# SCH_ralay.net
KiCad netlist of a schematic drawn in EasyEDA
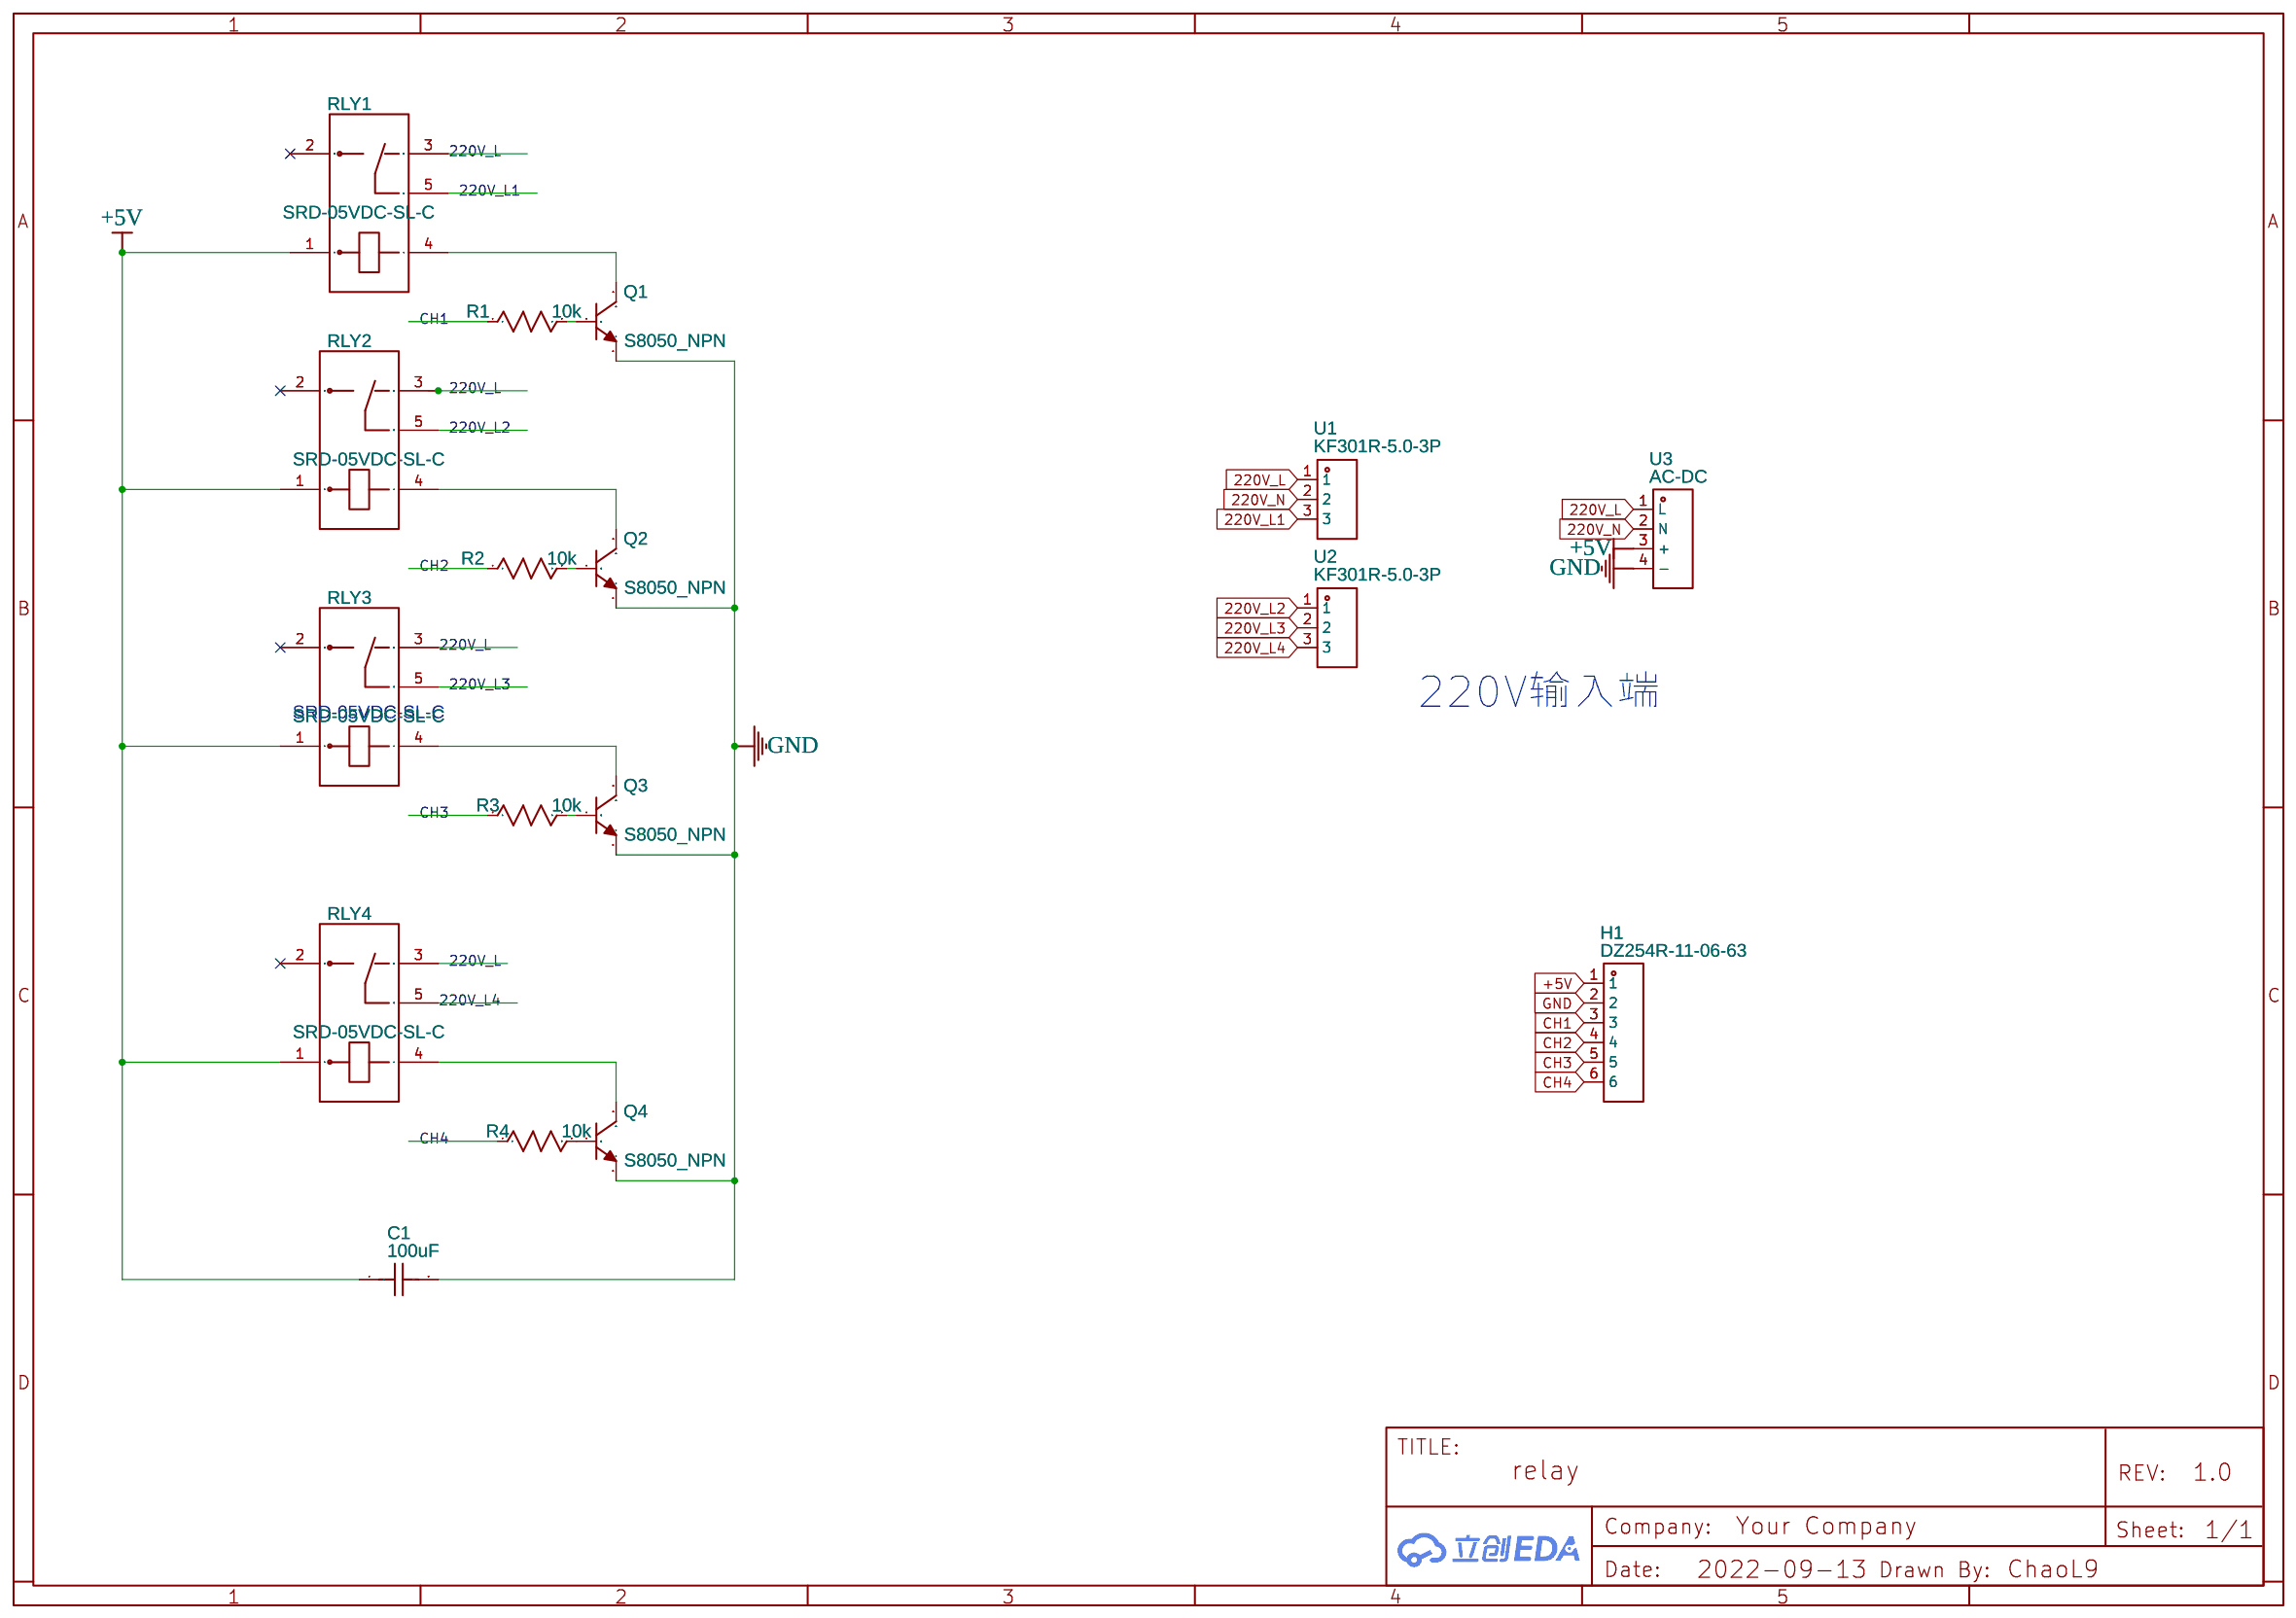
[diagram p0: schematic sheet]

(export (version "E")
  (design (tool "Eeschema 10.0.6"))
  (components
    (comp (ref "C1")
      (value "100uF")
      (fields
        (field (name "BOM_Manufacturer Part") "GRM21BC80E107ME15L")
        (field (name "BOM_Supplier Part") "C2167924")
      )
      (libsource (lib "") (part "GRM21BC80E107ME15L"))
    )
    (comp (ref "H1")
      (value "DZ254R-11-06-63")
      (fields (field (name "BOM_Supplier Part") "C2935912"))
      (libsource (lib "") (part "DZ254R-11-06-63"))
    )
    (comp (ref "Q1")
      (value "S8050_NPN")
      (fields (field (name "BOM_Manufacturer Part") "S8050") (field (name "BOM_Supplier Part") "C466625"))
      (libsource (lib "") (part "S8050_C466625"))
    )
    (comp (ref "Q2")
      (value "S8050_NPN")
      (fields (field (name "BOM_Manufacturer Part") "S8050") (field (name "BOM_Supplier Part") "C466625"))
      (libsource (lib "") (part "S8050_C466625"))
    )
    (comp (ref "Q3")
      (value "S8050_NPN")
      (fields (field (name "BOM_Manufacturer Part") "S8050") (field (name "BOM_Supplier Part") "C466625"))
      (libsource (lib "") (part "S8050_C466625"))
    )
    (comp (ref "Q4")
      (value "S8050_NPN")
      (fields (field (name "BOM_Manufacturer Part") "S8050") (field (name "BOM_Supplier Part") "C466625"))
      (libsource (lib "") (part "S8050_C466625"))
    )
    (comp (ref "R1") (value "10k") (libsource (lib "") (part "R_0603_US")))
    (comp (ref "R2") (value "10k") (libsource (lib "") (part "R_0603_US")))
    (comp (ref "R3") (value "10k") (libsource (lib "") (part "R_0603_US")))
    (comp (ref "R4") (value "10k") (libsource (lib "") (part "R_0603_US")))
    (comp (ref "RLY1")
      (value "SRD-05VDC-SL-C")
      (fields (field (name "BOM_Supplier Part") "C35449"))
      (libsource (lib "") (part "SRD-05VDC-SL-C"))
    )
    (comp (ref "RLY2")
      (value "SRD-05VDC-SL-C")
      (fields (field (name "BOM_Supplier Part") "C35449"))
      (libsource (lib "") (part "SRD-05VDC-SL-C"))
    )
    (comp (ref "RLY3")
      (value "SRD-05VDC-SL-C")
      (fields (field (name "BOM_Supplier Part") "C35449"))
      (libsource (lib "") (part "SRD-05VDC-SL-C"))
    )
    (comp (ref "RLY4")
      (value "SRD-05VDC-SL-C")
      (fields (field (name "BOM_Supplier Part") "C35449"))
      (libsource (lib "") (part "SRD-05VDC-SL-C"))
    )
    (comp (ref "U1")
      (value "KF301R-5.0-3P")
      (fields (field (name "BOM_Supplier Part") "C474884"))
      (libsource (lib "") (part "KF301R-5.0-3P"))
    )
    (comp (ref "U2")
      (value "KF301R-5.0-3P")
      (fields (field (name "BOM_Supplier Part") "C474884"))
      (libsource (lib "") (part "KF301R-5.0-3P"))
    )
    (comp (ref "U3") (value "AC-DC") (libsource (lib "") (part "AC-DC")))
  )
  (nets
    (net (code "1") (name "+5V") (class "Default")
      (node (ref "C1") (pin "1") (pinfunction "1_1") (pintype "unspecified"))
      (node (ref "H1") (pin "1") (pinfunction "1_1") (pintype "unspecified"))
      (node (ref "RLY1") (pin "1") (pinfunction "1_1") (pintype "input"))
      (node (ref "RLY2") (pin "1") (pinfunction "1_1") (pintype "input"))
      (node (ref "RLY3") (pin "1") (pinfunction "1_1") (pintype "input"))
      (node (ref "RLY4") (pin "1") (pinfunction "1_1") (pintype "input"))
      (node (ref "U3") (pin "3") (pinfunction "+_3") (pintype "unspecified"))
    )
    (net (code "2") (name "220V_L") (class "Default")
      (node (ref "RLY1") (pin "3") (pinfunction "3_3") (pintype "input"))
      (node (ref "RLY2") (pin "3") (pinfunction "3_3") (pintype "input"))
      (node (ref "RLY3") (pin "3") (pinfunction "3_3") (pintype "input"))
      (node (ref "RLY4") (pin "3") (pinfunction "3_3") (pintype "input"))
      (node (ref "U1") (pin "1") (pinfunction "1_1") (pintype "unspecified"))
      (node (ref "U3") (pin "1") (pinfunction "L_1") (pintype "unspecified"))
    )
    (net (code "3") (name "220V_L1") (class "Default")
      (node (ref "RLY1") (pin "5") (pinfunction "5_5") (pintype "input"))
      (node (ref "U1") (pin "3") (pinfunction "3_3") (pintype "unspecified"))
    )
    (net (code "4") (name "220V_L2") (class "Default")
      (node (ref "RLY2") (pin "5") (pinfunction "5_5") (pintype "input"))
      (node (ref "U2") (pin "1") (pinfunction "1_1") (pintype "unspecified"))
    )
    (net (code "5") (name "220V_L3") (class "Default")
      (node (ref "RLY3") (pin "5") (pinfunction "5_5") (pintype "input"))
      (node (ref "U2") (pin "2") (pinfunction "2_2") (pintype "unspecified"))
    )
    (net (code "6") (name "220V_L4") (class "Default")
      (node (ref "RLY4") (pin "5") (pinfunction "5_5") (pintype "input"))
      (node (ref "U2") (pin "3") (pinfunction "3_3") (pintype "unspecified"))
    )
    (net (code "7") (name "220V_N") (class "Default")
      (node (ref "U1") (pin "2") (pinfunction "2_2") (pintype "unspecified"))
      (node (ref "U3") (pin "2") (pinfunction "N_2") (pintype "unspecified"))
    )
    (net (code "8") (name "CH1") (class "Default")
      (node (ref "H1") (pin "3") (pinfunction "3_3") (pintype "unspecified"))
      (node (ref "R1") (pin "1") (pinfunction "1_1") (pintype "unspecified"))
    )
    (net (code "9") (name "CH2") (class "Default")
      (node (ref "H1") (pin "4") (pinfunction "4_4") (pintype "unspecified"))
      (node (ref "R2") (pin "1") (pinfunction "1_1") (pintype "unspecified"))
    )
    (net (code "10") (name "CH3") (class "Default")
      (node (ref "H1") (pin "5") (pinfunction "5_5") (pintype "unspecified"))
      (node (ref "R3") (pin "1") (pinfunction "1_1") (pintype "unspecified"))
    )
    (net (code "11") (name "CH4") (class "Default")
      (node (ref "H1") (pin "6") (pinfunction "6_6") (pintype "unspecified"))
      (node (ref "R4") (pin "1") (pinfunction "1_1") (pintype "unspecified"))
    )
    (net (code "12") (name "GND") (class "Default")
      (node (ref "C1") (pin "2") (pinfunction "2_2") (pintype "unspecified"))
      (node (ref "H1") (pin "2") (pinfunction "2_2") (pintype "unspecified"))
      (node (ref "Q1") (pin "2") (pinfunction "E_2") (pintype "unspecified"))
      (node (ref "Q2") (pin "2") (pinfunction "E_2") (pintype "unspecified"))
      (node (ref "Q3") (pin "2") (pinfunction "E_2") (pintype "unspecified"))
      (node (ref "Q4") (pin "2") (pinfunction "E_2") (pintype "unspecified"))
      (node (ref "U3") (pin "4") (pinfunction "-_4") (pintype "unspecified"))
    )
    (net (code "13") (name "Net-(Q1-B)") (class "Default")
      (node (ref "Q1") (pin "1") (pinfunction "B_1") (pintype "unspecified"))
      (node (ref "R1") (pin "2") (pinfunction "2_2") (pintype "unspecified"))
    )
    (net (code "14") (name "Net-(Q1-C)") (class "Default")
      (node (ref "Q1") (pin "3") (pinfunction "C_3") (pintype "unspecified"))
      (node (ref "RLY1") (pin "4") (pinfunction "4_4") (pintype "input"))
    )
    (net (code "15") (name "Net-(Q2-B)") (class "Default")
      (node (ref "Q2") (pin "1") (pinfunction "B_1") (pintype "unspecified"))
      (node (ref "R2") (pin "2") (pinfunction "2_2") (pintype "unspecified"))
    )
    (net (code "16") (name "Net-(Q2-C)") (class "Default")
      (node (ref "Q2") (pin "3") (pinfunction "C_3") (pintype "unspecified"))
      (node (ref "RLY2") (pin "4") (pinfunction "4_4") (pintype "input"))
    )
    (net (code "17") (name "Net-(Q3-B)") (class "Default")
      (node (ref "Q3") (pin "1") (pinfunction "B_1") (pintype "unspecified"))
      (node (ref "R3") (pin "2") (pinfunction "2_2") (pintype "unspecified"))
    )
    (net (code "18") (name "Net-(Q3-C)") (class "Default")
      (node (ref "Q3") (pin "3") (pinfunction "C_3") (pintype "unspecified"))
      (node (ref "RLY3") (pin "4") (pinfunction "4_4") (pintype "input"))
    )
    (net (code "19") (name "Net-(Q4-B)") (class "Default")
      (node (ref "Q4") (pin "1") (pinfunction "B_1") (pintype "unspecified"))
      (node (ref "R4") (pin "2") (pinfunction "2_2") (pintype "unspecified"))
    )
    (net (code "20") (name "Net-(Q4-C)") (class "Default")
      (node (ref "Q4") (pin "3") (pinfunction "C_3") (pintype "unspecified"))
      (node (ref "RLY4") (pin "4") (pinfunction "4_4") (pintype "input"))
    )
    (net (code "21") (name "unconnected-(RLY1-Pad2)") (class "Default")
      (node (ref "RLY1") (pin "2") (pinfunction "2_2") (pintype "input+no_connect"))
    )
    (net (code "22") (name "unconnected-(RLY2-Pad2)") (class "Default")
      (node (ref "RLY2") (pin "2") (pinfunction "2_2") (pintype "input+no_connect"))
    )
    (net (code "23") (name "unconnected-(RLY3-Pad2)") (class "Default")
      (node (ref "RLY3") (pin "2") (pinfunction "2_2") (pintype "input+no_connect"))
    )
    (net (code "24") (name "unconnected-(RLY4-Pad2)") (class "Default")
      (node (ref "RLY4") (pin "2") (pinfunction "2_2") (pintype "input+no_connect"))
    )
  )
)
